# Sheet1.net
KiCad netlist of a schematic drawn in Altium Designer
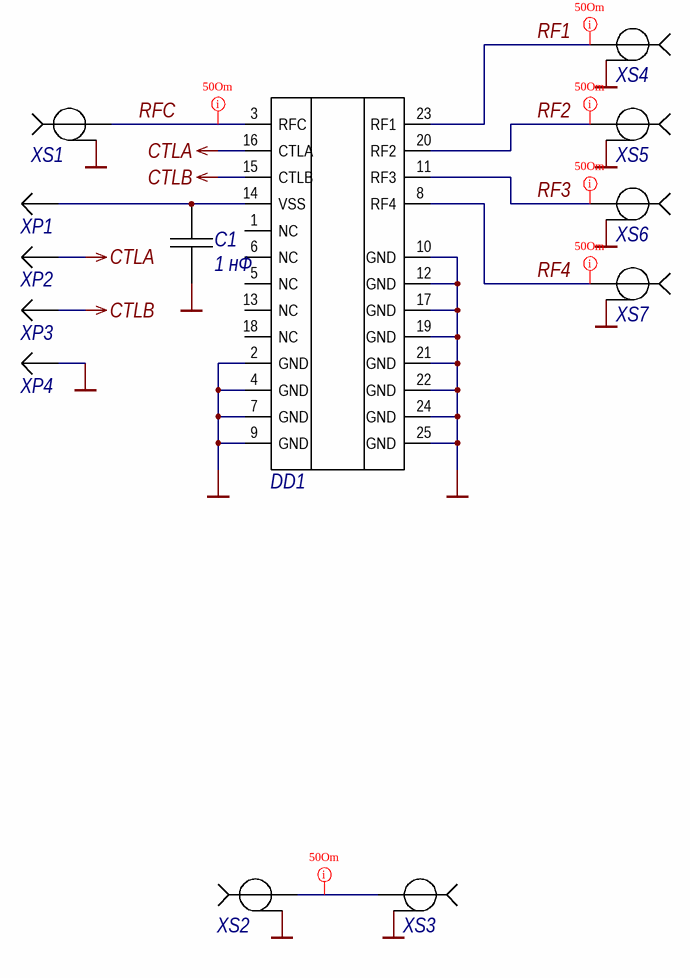
[diagram p0: Sheet1.SchDoc]

(export (version "E")
  (design (tool "Eeschema 10.0.6"))
  (components
    (comp (ref "C1")
      (value "С-0402 1 нФ 50 В C0G TDK Corporation")
      (footprint "FP-C0402--IPC_A")
      (fields
        (field (name "VOLTAGE") "50 В")
        (field (name "MANUFACTURER") "TDK Corporation")
        (field (name "CAPACITANCE") "1 нФ")
      )
      (libsource (lib "Schlib1") (part "C0402_1000pF_50V_C1005C0G1H102F050BA"))
    )
    (comp (ref "DD1")
      (value "HMC641ALP4 Analog Devices")
      (footprint "LFCSP 24 lead 4x4 mm")
      (description "IC RF SWITCH SP4T 20GHZ 24QFN")
      (fields (field (name "MANUFACTURER") "Analog Devices"))
      (libsource (lib "Schlib1") (part "EV1HMC641ALP4"))
    )
    (comp (ref "XP1")
      (value "HDR-M-2.54_1X1 Yuandi")
      (footprint "pinHeader-M-2.54_1X1")
      (description "HDR-M-2.54_1X1")
      (fields (field (name "MANUFACTURER") "Yuandi"))
      (libsource (lib "Schlib1") (part "HDR-M-2.54_1X1"))
    )
    (comp (ref "XP2")
      (value "HDR-M-2.54_1X1 Yuandi")
      (footprint "pinHeader-M-2.54_1X1")
      (description "HDR-M-2.54_1X1")
      (fields (field (name "MANUFACTURER") "Yuandi"))
      (libsource (lib "Schlib1") (part "HDR-M-2.54_1X1"))
    )
    (comp (ref "XP3")
      (value "HDR-M-2.54_1X1 Yuandi")
      (footprint "pinHeader-M-2.54_1X1")
      (description "HDR-M-2.54_1X1")
      (fields (field (name "MANUFACTURER") "Yuandi"))
      (libsource (lib "Schlib1") (part "HDR-M-2.54_1X1"))
    )
    (comp (ref "XP4")
      (value "HDR-M-2.54_1X1 Yuandi")
      (footprint "pinHeader-M-2.54_1X1")
      (description "HDR-M-2.54_1X1")
      (fields (field (name "MANUFACTURER") "Yuandi"))
      (libsource (lib "Schlib1") (part "HDR-M-2.54_1X1"))
    )
    (comp (ref "XS1")
      (value "901-10511-2 Amphenol RF")
      (footprint "SMA")
      (description "SMA Connector Jack, Female Socket 50 Ohms Board Edge, End Launch Solder")
      (fields (field (name "MANUFACTURER") "Amphenol RF"))
      (libsource (lib "Schlib1") (part "SMA_Amphenol RF_901-10511-2"))
    )
    (comp (ref "XS2")
      (value "901-10511-2 Amphenol RF")
      (footprint "SMA")
      (description "SMA Connector Jack, Female Socket 50 Ohms Board Edge, End Launch Solder")
      (fields (field (name "MANUFACTURER") "Amphenol RF"))
      (libsource (lib "Schlib1") (part "SMA_Amphenol RF_901-10511-2"))
    )
    (comp (ref "XS3")
      (value "901-10511-2 Amphenol RF")
      (footprint "SMA")
      (description "SMA Connector Jack, Female Socket 50 Ohms Board Edge, End Launch Solder")
      (fields (field (name "MANUFACTURER") "Amphenol RF"))
      (libsource (lib "Schlib1") (part "SMA_Amphenol RF_901-10511-2"))
    )
    (comp (ref "XS4")
      (value "901-10511-2 Amphenol RF")
      (footprint "SMA")
      (description "SMA Connector Jack, Female Socket 50 Ohms Board Edge, End Launch Solder")
      (fields (field (name "MANUFACTURER") "Amphenol RF"))
      (libsource (lib "Schlib1") (part "SMA_Amphenol RF_901-10511-2"))
    )
    (comp (ref "XS5")
      (value "901-10511-2 Amphenol RF")
      (footprint "SMA")
      (description "SMA Connector Jack, Female Socket 50 Ohms Board Edge, End Launch Solder")
      (fields (field (name "MANUFACTURER") "Amphenol RF"))
      (libsource (lib "Schlib1") (part "SMA_Amphenol RF_901-10511-2"))
    )
    (comp (ref "XS6")
      (value "901-10511-2 Amphenol RF")
      (footprint "SMA")
      (description "SMA Connector Jack, Female Socket 50 Ohms Board Edge, End Launch Solder")
      (fields (field (name "MANUFACTURER") "Amphenol RF"))
      (libsource (lib "Schlib1") (part "SMA_Amphenol RF_901-10511-2"))
    )
    (comp (ref "XS7")
      (value "901-10511-2 Amphenol RF")
      (footprint "SMA")
      (description "SMA Connector Jack, Female Socket 50 Ohms Board Edge, End Launch Solder")
      (fields (field (name "MANUFACTURER") "Amphenol RF"))
      (libsource (lib "Schlib1") (part "SMA_Amphenol RF_901-10511-2"))
    )
  )
  (nets
    (net (code "1") (name "/RF1") (class "Default")
      (node (ref "DD1") (pin "23") (pinfunction "RF1_23") (pintype "passive"))
      (node (ref "XS4") (pin "1") (pinfunction "1_1") (pintype "passive"))
    )
    (net (code "2") (name "/RF2") (class "Default")
      (node (ref "DD1") (pin "20") (pinfunction "RF2_20") (pintype "passive"))
      (node (ref "XS5") (pin "1") (pinfunction "1_1") (pintype "passive"))
    )
    (net (code "3") (name "/RF3") (class "Default")
      (node (ref "DD1") (pin "11") (pinfunction "RF3_11") (pintype "passive"))
      (node (ref "XS6") (pin "1") (pinfunction "1_1") (pintype "passive"))
    )
    (net (code "4") (name "/RF4") (class "Default")
      (node (ref "DD1") (pin "8") (pinfunction "RF4_8") (pintype "passive"))
      (node (ref "XS7") (pin "1") (pinfunction "1_1") (pintype "passive"))
    )
    (net (code "5") (name "/RFC") (class "Default")
      (node (ref "DD1") (pin "3") (pinfunction "RFC_3") (pintype "passive"))
      (node (ref "XS1") (pin "1") (pinfunction "1_1") (pintype "passive"))
    )
    (net (code "6") (name "CTLA") (class "Default")
      (node (ref "DD1") (pin "16") (pinfunction "CTLA_16") (pintype "passive"))
      (node (ref "XP2") (pin "1") (pinfunction "1_1") (pintype "passive"))
    )
    (net (code "7") (name "CTLB") (class "Default")
      (node (ref "DD1") (pin "15") (pinfunction "CTLB_15") (pintype "passive"))
      (node (ref "XP3") (pin "1") (pinfunction "1_1") (pintype "passive"))
    )
    (net (code "8") (name "GND") (class "Default")
      (node (ref "C1") (pin "2") (pintype "power_in"))
      (node (ref "DD1") (pin "10") (pinfunction "GND_10") (pintype "power_in"))
      (node (ref "DD1") (pin "12") (pinfunction "GND_12") (pintype "power_in"))
      (node (ref "DD1") (pin "17") (pinfunction "GND_17") (pintype "power_in"))
      (node (ref "DD1") (pin "19") (pinfunction "GND_19") (pintype "power_in"))
      (node (ref "DD1") (pin "2") (pinfunction "GND_2") (pintype "power_in"))
      (node (ref "DD1") (pin "21") (pinfunction "GND_21") (pintype "power_in"))
      (node (ref "DD1") (pin "22") (pinfunction "GND_22") (pintype "power_in"))
      (node (ref "DD1") (pin "24") (pinfunction "GND_24") (pintype "power_in"))
      (node (ref "DD1") (pin "25") (pinfunction "GND_25") (pintype "power_in"))
      (node (ref "DD1") (pin "4") (pinfunction "GND_4") (pintype "power_in"))
      (node (ref "DD1") (pin "7") (pinfunction "GND_7") (pintype "power_in"))
      (node (ref "DD1") (pin "9") (pinfunction "GND_9") (pintype "power_in"))
      (node (ref "XP4") (pin "1") (pinfunction "1_1") (pintype "passive"))
      (node (ref "XS1") (pin "2") (pinfunction "2_2") (pintype "passive"))
      (node (ref "XS2") (pin "2") (pinfunction "2_2") (pintype "passive"))
      (node (ref "XS3") (pin "2") (pinfunction "2_2") (pintype "passive"))
      (node (ref "XS4") (pin "2") (pinfunction "2_2") (pintype "passive"))
      (node (ref "XS5") (pin "2") (pinfunction "2_2") (pintype "passive"))
      (node (ref "XS6") (pin "2") (pinfunction "2_2") (pintype "passive"))
      (node (ref "XS7") (pin "2") (pinfunction "2_2") (pintype "passive"))
    )
    (net (code "9") (name "Net-(DD1-VSS)") (class "Default")
      (node (ref "C1") (pin "1") (pintype "power_in"))
      (node (ref "DD1") (pin "14") (pinfunction "VSS_14") (pintype "power_in"))
      (node (ref "XP1") (pin "1") (pinfunction "1_1") (pintype "passive"))
    )
    (net (code "10") (name "Net-(XS2-Pad1)") (class "Default")
      (node (ref "XS2") (pin "1") (pinfunction "1_1") (pintype "passive"))
      (node (ref "XS3") (pin "1") (pinfunction "1_1") (pintype "passive"))
    )
    (net (code "11") (name "unconnected-(DD1-NC-Pad1)") (class "Default")
      (node (ref "DD1") (pin "1") (pinfunction "NC_1") (pintype "passive"))
    )
    (net (code "12") (name "unconnected-(DD1-NC-Pad5)") (class "Default")
      (node (ref "DD1") (pin "5") (pinfunction "NC_5") (pintype "passive"))
    )
    (net (code "13") (name "unconnected-(DD1-NC-Pad6)") (class "Default")
      (node (ref "DD1") (pin "6") (pinfunction "NC_6") (pintype "passive"))
    )
    (net (code "14") (name "unconnected-(DD1-NC-Pad13)") (class "Default")
      (node (ref "DD1") (pin "13") (pinfunction "NC_13") (pintype "passive"))
    )
    (net (code "15") (name "unconnected-(DD1-NC-Pad18)") (class "Default")
      (node (ref "DD1") (pin "18") (pinfunction "NC_18") (pintype "passive"))
    )
  )
)
